# ppc_serial.net
KiCad netlist of a schematic drawn in Altium Designer
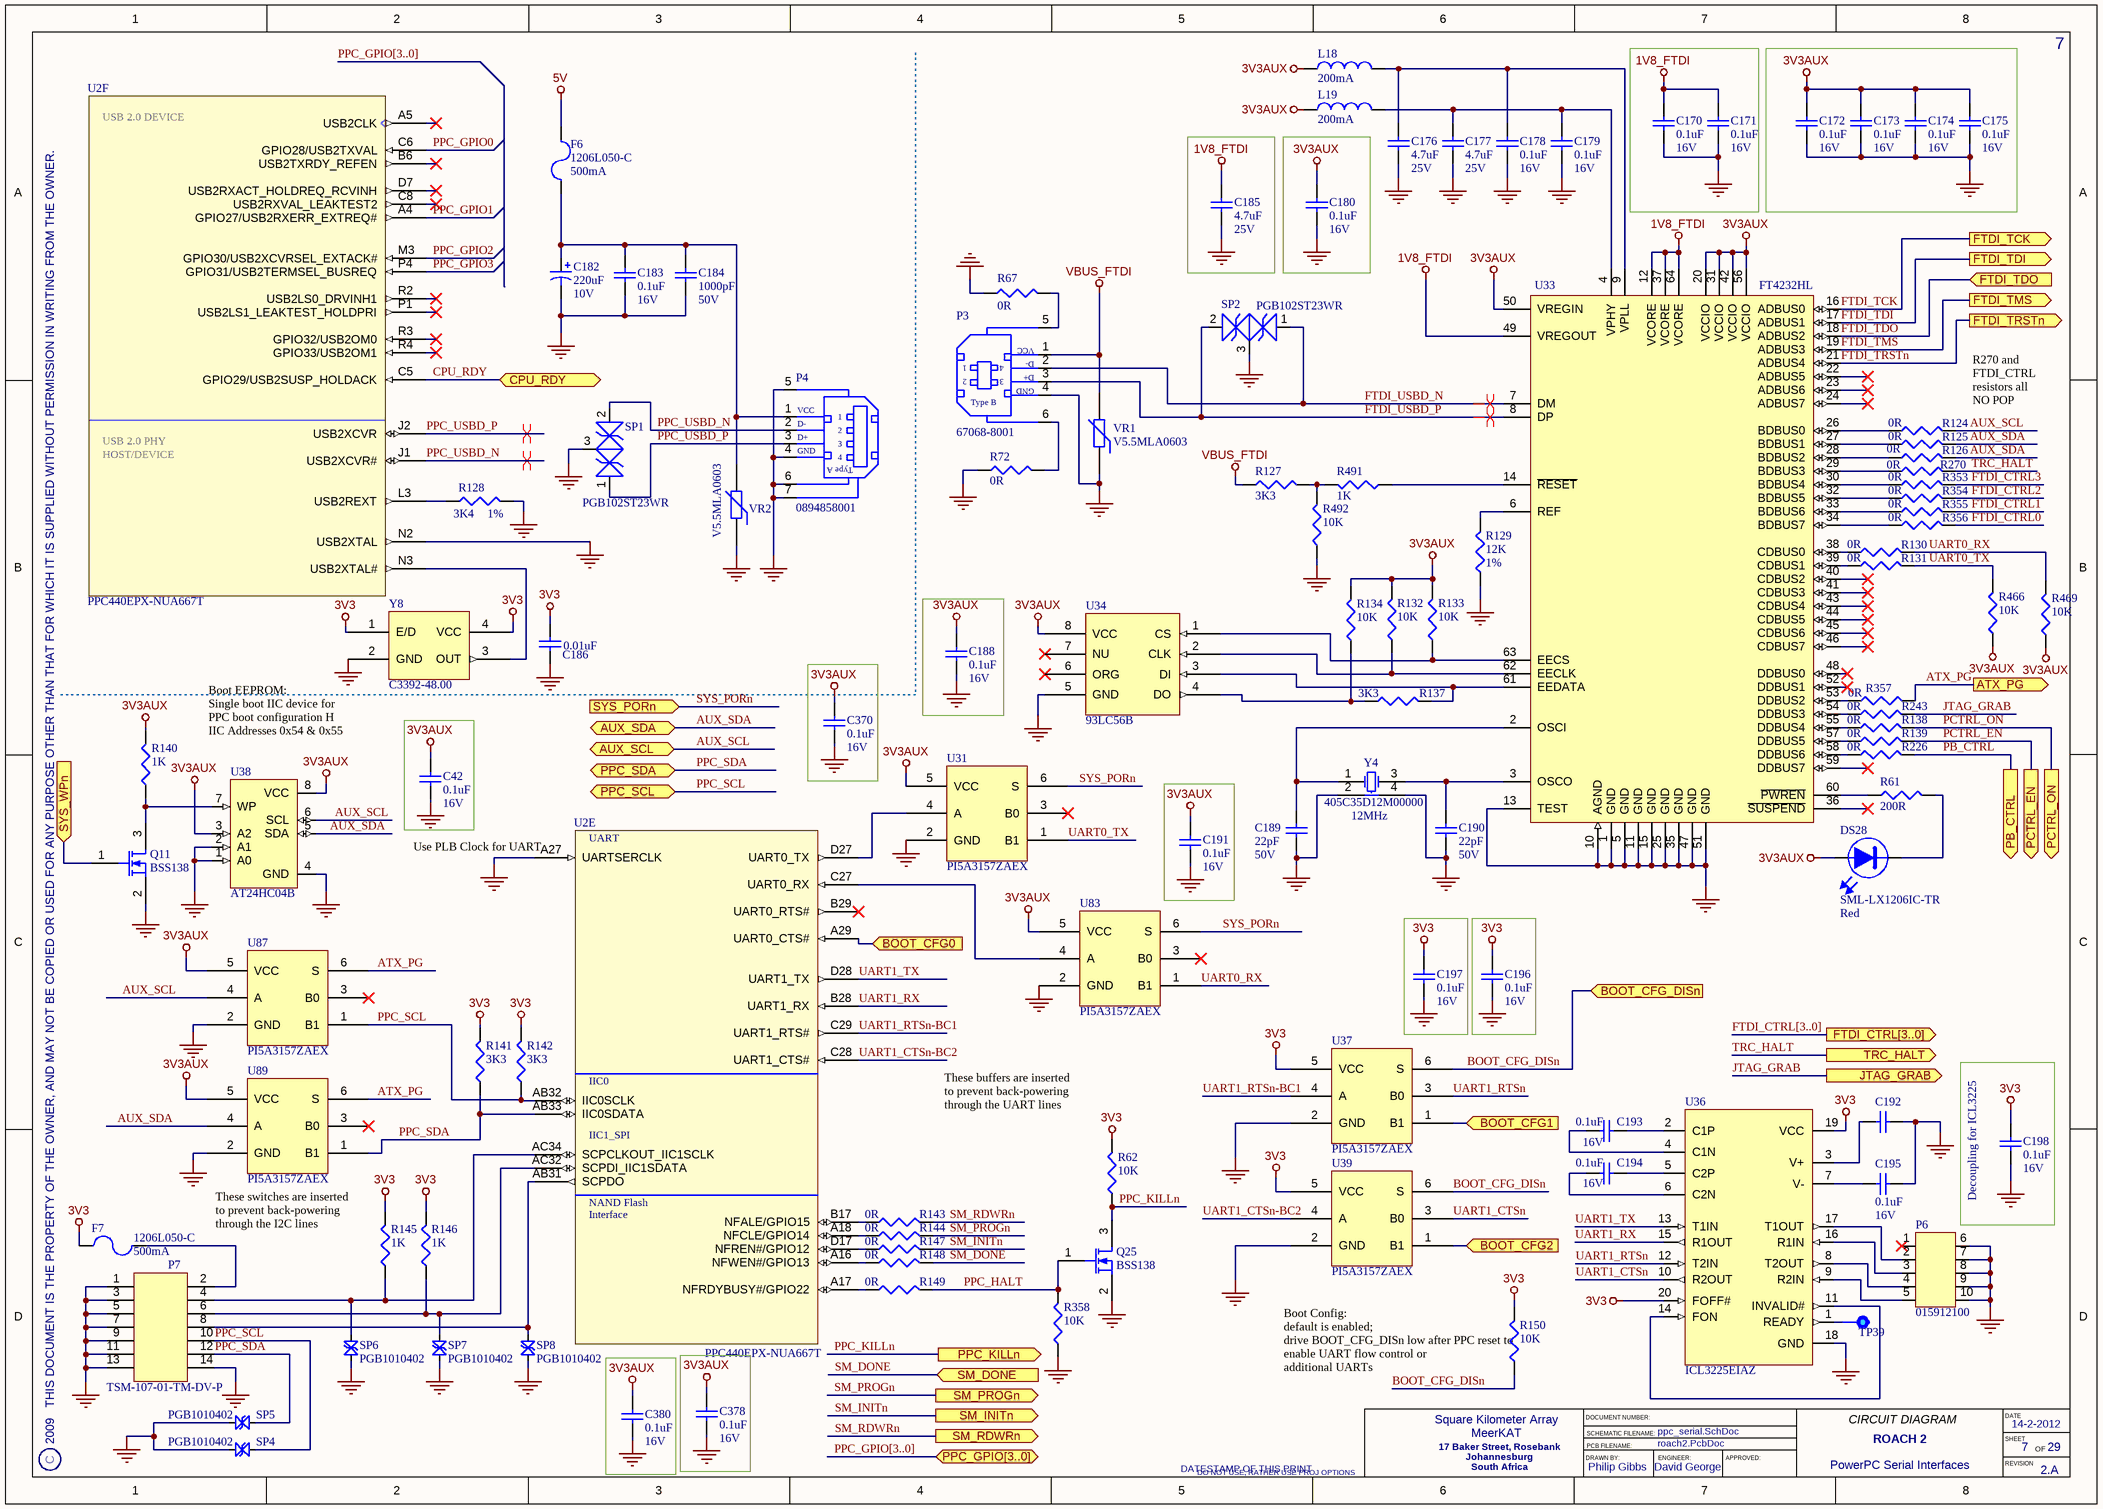
[diagram p0: ppc_serial.SchDoc]

(export (version "E")
  (design (tool "Eeschema 10.0.6"))
  (components
    (comp (ref "C42")
      (value "0.1uF")
      (footprint "CAPC1005X60L")
      (description "0.1uF, Ceramic Capacitor")
      (fields
        (field (name "RATING") "16V")
        (field (name "MANUFACTURER") "VENKEL")
        (field (name "PARTNUM") "C0402X7R160-104KN")
      )
      (libsource (lib "altium_db") (part "CapStd"))
    )
    (comp (ref "C170")
      (value "0.1uF")
      (footprint "CAPC1005X60L")
      (description "0.1uF, Ceramic Capacitor")
      (fields
        (field (name "RATING") "16V")
        (field (name "MANUFACTURER") "VENKEL")
        (field (name "PARTNUM") "C0402X7R160-104KN")
      )
      (libsource (lib "altium_db") (part "CapStd"))
    )
    (comp (ref "C171")
      (value "0.1uF")
      (footprint "CAPC1005X60L")
      (description "0.1uF, Ceramic Capacitor")
      (fields
        (field (name "RATING") "16V")
        (field (name "MANUFACTURER") "VENKEL")
        (field (name "PARTNUM") "C0402X7R160-104KN")
      )
      (libsource (lib "altium_db") (part "CapStd"))
    )
    (comp (ref "C172")
      (value "0.1uF")
      (footprint "CAPC1005X60L")
      (description "0.1uF, Ceramic Capacitor")
      (fields
        (field (name "RATING") "16V")
        (field (name "MANUFACTURER") "VENKEL")
        (field (name "PARTNUM") "C0402X7R160-104KN")
      )
      (libsource (lib "altium_db") (part "CapStd"))
    )
    (comp (ref "C173")
      (value "0.1uF")
      (footprint "CAPC1005X60L")
      (description "0.1uF, Ceramic Capacitor")
      (fields
        (field (name "RATING") "16V")
        (field (name "MANUFACTURER") "VENKEL")
        (field (name "PARTNUM") "C0402X7R160-104KN")
      )
      (libsource (lib "altium_db") (part "CapStd"))
    )
    (comp (ref "C174")
      (value "0.1uF")
      (footprint "CAPC1005X60L")
      (description "0.1uF, Ceramic Capacitor")
      (fields
        (field (name "RATING") "16V")
        (field (name "MANUFACTURER") "VENKEL")
        (field (name "PARTNUM") "C0402X7R160-104KN")
      )
      (libsource (lib "altium_db") (part "CapStd"))
    )
    (comp (ref "C175")
      (value "0.1uF")
      (footprint "CAPC1005X60L")
      (description "0.1uF, Ceramic Capacitor")
      (fields
        (field (name "RATING") "16V")
        (field (name "MANUFACTURER") "VENKEL")
        (field (name "PARTNUM") "C0402X7R160-104KN")
      )
      (libsource (lib "altium_db") (part "CapStd"))
    )
    (comp (ref "C176")
      (value "4.7uF")
      (footprint "CAPC2012X127L")
      (description "4.7uF, Ceramic Capacitor")
      (fields
        (field (name "RATING") "25V")
        (field (name "MANUFACTURER") "MURATA")
        (field (name "PARTNUM") "GRM21BR61E475KA12K")
      )
      (libsource (lib "altium_db") (part "CapStd"))
    )
    (comp (ref "C177")
      (value "4.7uF")
      (footprint "CAPC2012X127L")
      (description "4.7uF, Ceramic Capacitor")
      (fields
        (field (name "RATING") "25V")
        (field (name "MANUFACTURER") "MURATA")
        (field (name "PARTNUM") "GRM21BR61E475KA12K")
      )
      (libsource (lib "altium_db") (part "CapStd"))
    )
    (comp (ref "C178")
      (value "0.1uF")
      (footprint "CAPC1005X60L")
      (description "0.1uF, Ceramic Capacitor")
      (fields
        (field (name "RATING") "16V")
        (field (name "MANUFACTURER") "VENKEL")
        (field (name "PARTNUM") "C0402X7R160-104KN")
      )
      (libsource (lib "altium_db") (part "CapStd"))
    )
    (comp (ref "C179")
      (value "0.1uF")
      (footprint "CAPC1005X60L")
      (description "0.1uF, Ceramic Capacitor")
      (fields
        (field (name "RATING") "16V")
        (field (name "MANUFACTURER") "VENKEL")
        (field (name "PARTNUM") "C0402X7R160-104KN")
      )
      (libsource (lib "altium_db") (part "CapStd"))
    )
    (comp (ref "C180")
      (value "0.1uF")
      (footprint "CAPC1005X60L")
      (description "0.1uF, Ceramic Capacitor")
      (fields
        (field (name "RATING") "16V")
        (field (name "MANUFACTURER") "VENKEL")
        (field (name "PARTNUM") "C0402X7R160-104KN")
      )
      (libsource (lib "altium_db") (part "CapStd"))
    )
    (comp (ref "C182")
      (value "220uF")
      (footprint "CAPMP7343X430L")
      (description "220uF, Solid Tantalum Chip Capacitor")
      (fields
        (field (name "RATING") "10V")
        (field (name "MANUFACTURER") "KEMET")
        (field (name "PARTNUM") "T491X227M010AT")
      )
      (libsource (lib "altium_db") (part "CapPol"))
    )
    (comp (ref "C183")
      (value "0.1uF")
      (footprint "CAPC1005X60L")
      (description "0.1uF, Ceramic Capacitor")
      (fields
        (field (name "RATING") "16V")
        (field (name "MANUFACTURER") "VENKEL")
        (field (name "PARTNUM") "C0402X7R160-104KN")
      )
      (libsource (lib "altium_db") (part "CapStd"))
    )
    (comp (ref "C184")
      (value "1000pF")
      (footprint "CAPC1005X55L")
      (description "1000pF, Ceramic Capacitor")
      (fields
        (field (name "RATING") "50V")
        (field (name "MANUFACTURER") "MURATA")
        (field (name "PARTNUM") "GRM155R61H102KA01D")
      )
      (libsource (lib "altium_db") (part "CapStd"))
    )
    (comp (ref "C185")
      (value "4.7uF")
      (footprint "CAPC2012X127L")
      (description "4.7uF, Ceramic Capacitor")
      (fields
        (field (name "RATING") "25V")
        (field (name "MANUFACTURER") "MURATA")
        (field (name "PARTNUM") "GRM21BR61E475KA12K")
      )
      (libsource (lib "altium_db") (part "CapStd"))
    )
    (comp (ref "C186")
      (value "0.01uF")
      (footprint "CAPC1005X55L")
      (description "0.01uF, Ceramic Capacitor")
      (fields (field (name "MANUFACTURER") "MURATA") (field (name "PARTNUM") "GRM155R71E103KA01D"))
      (libsource (lib "Altium_DB") (part "CapStd"))
    )
    (comp (ref "C188")
      (value "0.1uF")
      (footprint "CAPC1005X60L")
      (description "0.1uF, Ceramic Capacitor")
      (fields
        (field (name "RATING") "16V")
        (field (name "MANUFACTURER") "VENKEL")
        (field (name "PARTNUM") "C0402X7R160-104KN")
      )
      (libsource (lib "altium_db") (part "CapStd"))
    )
    (comp (ref "C189")
      (value "22pF")
      (footprint "CAPC1005X55L")
      (description "22pF, Ceramic Capacitor")
      (fields
        (field (name "RATING") "50V")
        (field (name "MANUFACTURER") "MURATA")
        (field (name "PARTNUM") "GRM1555C1H220JA01D")
      )
      (libsource (lib "altium_db") (part "CapStd"))
    )
    (comp (ref "C190")
      (value "22pF")
      (footprint "CAPC1005X55L")
      (description "22pF, Ceramic Capacitor")
      (fields
        (field (name "RATING") "50V")
        (field (name "MANUFACTURER") "MURATA")
        (field (name "PARTNUM") "GRM1555C1H220JA01D")
      )
      (libsource (lib "altium_db") (part "CapStd"))
    )
    (comp (ref "C191")
      (value "0.1uF")
      (footprint "CAPC1005X60L")
      (description "0.1uF, Ceramic Capacitor")
      (fields
        (field (name "RATING") "16V")
        (field (name "MANUFACTURER") "VENKEL")
        (field (name "PARTNUM") "C0402X7R160-104KN")
      )
      (libsource (lib "altium_db") (part "CapStd"))
    )
    (comp (ref "C192")
      (value "~")
      (footprint "CAPC1005X60L")
      (description "0.1uF, Ceramic Capacitor")
      (fields (field (name "MANUFACTURER") "VENKEL") (field (name "PARTNUM") "C0402X7R160-104KN"))
      (libsource (lib "altium_db") (part "CapStd"))
    )
    (comp (ref "C193")
      (value "0.1uF")
      (footprint "CAPC1005X60L")
      (description "0.1uF, Ceramic Capacitor")
      (fields
        (field (name "RATING") "16V")
        (field (name "MANUFACTURER") "VENKEL")
        (field (name "PARTNUM") "C0402X7R160-104KN")
      )
      (libsource (lib "altium_db") (part "CapStd"))
    )
    (comp (ref "C194")
      (value "0.1uF")
      (footprint "CAPC1005X60L")
      (description "0.1uF, Ceramic Capacitor")
      (fields
        (field (name "RATING") "16V")
        (field (name "MANUFACTURER") "VENKEL")
        (field (name "PARTNUM") "C0402X7R160-104KN")
      )
      (libsource (lib "altium_db") (part "CapStd"))
    )
    (comp (ref "C195")
      (value "0.1uF")
      (footprint "CAPC1005X60L")
      (description "0.1uF, Ceramic Capacitor")
      (fields
        (field (name "RATING") "16V")
        (field (name "MANUFACTURER") "VENKEL")
        (field (name "PARTNUM") "C0402X7R160-104KN")
      )
      (libsource (lib "altium_db") (part "CapStd"))
    )
    (comp (ref "C196")
      (value "0.1uF")
      (footprint "CAPC1005X60L")
      (description "0.1uF, Ceramic Capacitor")
      (fields
        (field (name "RATING") "16V")
        (field (name "MANUFACTURER") "VENKEL")
        (field (name "PARTNUM") "C0402X7R160-104KN")
      )
      (libsource (lib "altium_db") (part "CapStd"))
    )
    (comp (ref "C197")
      (value "0.1uF")
      (footprint "CAPC1005X60L")
      (description "0.1uF, Ceramic Capacitor")
      (fields
        (field (name "RATING") "16V")
        (field (name "MANUFACTURER") "VENKEL")
        (field (name "PARTNUM") "C0402X7R160-104KN")
      )
      (libsource (lib "altium_db") (part "CapStd"))
    )
    (comp (ref "C198")
      (value "0.1uF")
      (footprint "CAPC1005X60L")
      (description "0.1uF, Ceramic Capacitor")
      (fields
        (field (name "RATING") "16V")
        (field (name "MANUFACTURER") "VENKEL")
        (field (name "PARTNUM") "C0402X7R160-104KN")
      )
      (libsource (lib "altium_db") (part "CapStd"))
    )
    (comp (ref "C370")
      (value "0.1uF")
      (footprint "CAPC1005X60L")
      (description "0.1uF, Ceramic Capacitor")
      (fields
        (field (name "RATING") "16V")
        (field (name "MANUFACTURER") "VENKEL")
        (field (name "PARTNUM") "C0402X7R160-104KN")
      )
      (libsource (lib "altium_db") (part "CapStd"))
    )
    (comp (ref "C378")
      (value "0.1uF")
      (footprint "CAPC1005X60L")
      (description "0.1uF, Ceramic Capacitor")
      (fields
        (field (name "RATING") "16V")
        (field (name "MANUFACTURER") "VENKEL")
        (field (name "PARTNUM") "C0402X7R160-104KN")
      )
      (libsource (lib "altium_db") (part "CapStd"))
    )
    (comp (ref "C380")
      (value "0.1uF")
      (footprint "CAPC1005X60L")
      (description "0.1uF, Ceramic Capacitor")
      (fields
        (field (name "RATING") "16V")
        (field (name "MANUFACTURER") "VENKEL")
        (field (name "PARTNUM") "C0402X7R160-104KN")
      )
      (libsource (lib "altium_db") (part "CapStd"))
    )
    (comp (ref "DS28")
      (value "SML-LX1206IC-TR")
      (footprint "LEDC3216X120N")
      (description "Red, Surface mount, LED, 1206")
      (fields (field (name "COLOUR") "Red") (field (name "MANUFACTURER") "LUMEX"))
      (libsource (lib "altium_db") (part "LEDSTD"))
    )
    (comp (ref "F6")
      (value "1206L050-C")
      (footprint "FUSMC3215X145")
      (description "Resettable, Surface mount Fuse")
      (fields
        (field (name "MANUFACTURER") "Littelfuse")
        (field (name "PARTNUM") "1206L050-C")
        (field (name "RATING") "500mA")
      )
      (libsource (lib "altium_db") (part "FuseStd"))
    )
    (comp (ref "F7")
      (value "1206L050-C")
      (footprint "FUSMC3215X145")
      (description "Resettable, Surface mount Fuse")
      (fields
        (field (name "MANUFACTURER") "Littelfuse")
        (field (name "PARTNUM") "1206L050-C")
        (field (name "RATING") "500mA")
      )
      (libsource (lib "altium_db") (part "FuseStd"))
    )
    (comp (ref "L18")
      (value "600R")
      (footprint "INDC2012X130L")
      (description "600 Ohm, Chip Ferrite Bead")
      (fields
        (field (name "MANUFACTURER") "Murata")
        (field (name "PARTNUM") "BLM21BD601SN1")
        (field (name "RATING") "200mA")
      )
      (libsource (lib "altium_db") (part "IndStd"))
    )
    (comp (ref "L19")
      (value "600R")
      (footprint "INDC2012X130L")
      (description "600 Ohm, Chip Ferrite Bead")
      (fields
        (field (name "MANUFACTURER") "Murata")
        (field (name "PARTNUM") "BLM21BD601SN1")
        (field (name "RATING") "200mA")
      )
      (libsource (lib "altium_db") (part "IndStd"))
    )
    (comp (ref "P3")
      (value "67068-8001")
      (footprint "MOLEX_67068-8001")
      (description "Right angle, Through-hole, USB Type B Receptacle")
      (fields (field (name "PARTNUM") "67068-8001") (field (name "MANUFACTURER") "Molex"))
      (libsource (lib "altium_db") (part "USB_TYPE_B_GENERIC"))
    )
    (comp (ref "P4")
      (value "USB_TYPEA_TYCO")
      (footprint "MOLEX_0894858001")
      (description "Right angle, Through-hole, USB Type A Receptacle")
      (fields (field (name "PARTNUM") "0894858001"))
      (libsource (lib "altium_db") (part "0894858001"))
    )
    (comp (ref "P6")
      (value "015912100")
      (footprint "MOLEX_0015912100")
      (description "2x5, 2.54 mm Pitch, Male Header")
      (fields (field (name "MANUFACTURER") "Molex") (field (name "PARTNUM") "015912100"))
      (libsource (lib "altium_db") (part "con_hdr_2x5"))
    )
    (comp (ref "P7")
      (value "TSM-107-01-TM-DV-P")
      (footprint "SAMTEC_TSM-107-01-TM-DV-P")
      (description "2x7, 2.54 mm Pitch, Male Header")
      (fields (field (name "PARTNUM") "TSM-107-01-TM-DV-P") (field (name "MANUFACTURER") "SAMTEC"))
      (libsource (lib "altium_db") (part "con_hdr_2x7"))
    )
    (comp (ref "Q11")
      (value "BSS138")
      (footprint "SOT95P245X110-3N")
      (description "N-Channel Logic Level Enhancement Mode Field Effect Transistor")
      (fields (field (name "MANUFACTURER") "Fairchild Semiconductor"))
      (libsource (lib "altium_db") (part "BSS138"))
    )
    (comp (ref "Q25")
      (value "BSS138")
      (footprint "SOT95P245X110-3N")
      (description "N-Channel Logic Level Enhancement Mode Field Effect Transistor")
      (fields (field (name "MANUFACTURER") "Fairchild Semiconductor"))
      (libsource (lib "altium_db") (part "BSS138"))
    )
    (comp (ref "R61")
      (value "200R")
      (footprint "RESC1005X40L")
      (description "200R, 1.1mm x 0.5mm, Thick Film Resistor")
      (fields (field (name "MANUFACTURER") "ROYALOHM") (field (name "PARTNUM") "0402WGF0201T1E"))
      (libsource (lib "altium_db") (part "ResStd"))
    )
    (comp (ref "R62")
      (value "10K")
      (footprint "RESC1005X40L")
      (description "10K, 1.1mm x 0.5mm, Thick Film Resistor")
      (fields (field (name "MANUFACTURER") "ROYALOHM") (field (name "PARTNUM") "0402WGJ0103T1E"))
      (libsource (lib "altium_db") (part "ResStd"))
    )
    (comp (ref "R67")
      (value "0R")
      (footprint "RESC1005X40L")
      (description "0R, 1.1mm x 0.5mm, Thick Film Resistor")
      (fields (field (name "MANUFACTURER") "ROYALOHM") (field (name "PARTNUM") "0402WG00000T1E"))
      (libsource (lib "altium_db") (part "ResStd"))
    )
    (comp (ref "R72")
      (value "0R")
      (footprint "RESC1005X40L")
      (description "0R, 1.1mm x 0.5mm, Thick Film Resistor")
      (fields (field (name "MANUFACTURER") "ROYALOHM") (field (name "PARTNUM") "0402WG00000T1E"))
      (libsource (lib "altium_db") (part "ResStd"))
    )
    (comp (ref "R124")
      (value "0R")
      (footprint "RESC1005X40L")
      (description "0R, 1.1mm x 0.5mm, Thick Film Resistor")
      (fields (field (name "MANUFACTURER") "ROYALOHM") (field (name "PARTNUM") "0402WG00000T1E"))
      (libsource (lib "altium_db") (part "ResStd"))
    )
    (comp (ref "R125")
      (value "0R")
      (footprint "RESC1005X40L")
      (description "0R, 1.1mm x 0.5mm, Thick Film Resistor")
      (fields (field (name "MANUFACTURER") "ROYALOHM") (field (name "PARTNUM") "0402WG00000T1E"))
      (libsource (lib "altium_db") (part "ResStd"))
    )
    (comp (ref "R126")
      (value "0R")
      (footprint "RESC1005X40L")
      (description "0R, 1.1mm x 0.5mm, Thick Film Resistor")
      (fields (field (name "MANUFACTURER") "ROYALOHM") (field (name "PARTNUM") "0402WG00000T1E"))
      (libsource (lib "altium_db") (part "ResStd"))
    )
    (comp (ref "R127")
      (value "3K3")
      (footprint "RESC1005X40L")
      (description "3K3, 1.1mm x 0.5mm, Thick Film Resistor")
      (fields (field (name "MANUFACTURER") "ROYALOHM") (field (name "PARTNUM") "0402WGJ0332T1E"))
      (libsource (lib "altium_db") (part "ResStd"))
    )
    (comp (ref "R128")
      (value "3K4")
      (footprint "RESC1005X40L")
      (description "3K4, 1.1mm x 0.5mm, Thick Film Resistor")
      (fields
        (field (name "MANUFACTURER") "ROYALOHM")
        (field (name "PARTNUM") "0402WGF0342T1E")
        (field (name "TOLERANCE") "1%")
      )
      (libsource (lib "altium_db") (part "ResStd"))
    )
    (comp (ref "R129")
      (value "12K")
      (footprint "RESC1005X40L")
      (description "12K, 1.1mm x 0.5mm, Thick Film Resistor")
      (fields
        (field (name "MANUFACTURER") "ROYALOHM")
        (field (name "PARTNUM") "0402WGF0123T1E")
        (field (name "TOLERANCE") "1%")
      )
      (libsource (lib "altium_db") (part "ResStd"))
    )
    (comp (ref "R130")
      (value "0R")
      (footprint "RESC1005X40L")
      (description "0R, 1.1mm x 0.5mm, Thick Film Resistor")
      (fields (field (name "MANUFACTURER") "ROYALOHM") (field (name "PARTNUM") "0402WG00000T1E"))
      (libsource (lib "altium_db") (part "ResStd"))
    )
    (comp (ref "R131")
      (value "0R")
      (footprint "RESC1005X40L")
      (description "0R, 1.1mm x 0.5mm, Thick Film Resistor")
      (fields (field (name "MANUFACTURER") "ROYALOHM") (field (name "PARTNUM") "0402WG00000T1E"))
      (libsource (lib "altium_db") (part "ResStd"))
    )
    (comp (ref "R132")
      (value "10K")
      (footprint "RESC1005X40L")
      (description "10K, 1.1mm x 0.5mm, Thick Film Resistor")
      (fields (field (name "MANUFACTURER") "ROYALOHM") (field (name "PARTNUM") "0402WGJ0103T1E"))
      (libsource (lib "altium_db") (part "ResStd"))
    )
    (comp (ref "R133")
      (value "10K")
      (footprint "RESC1005X40L")
      (description "10K, 1.1mm x 0.5mm, Thick Film Resistor")
      (fields (field (name "MANUFACTURER") "ROYALOHM") (field (name "PARTNUM") "0402WGJ0103T1E"))
      (libsource (lib "altium_db") (part "ResStd"))
    )
    (comp (ref "R134")
      (value "10K")
      (footprint "RESC1005X40L")
      (description "10K, 1.1mm x 0.5mm, Thick Film Resistor")
      (fields (field (name "MANUFACTURER") "ROYALOHM") (field (name "PARTNUM") "0402WGJ0103T1E"))
      (libsource (lib "altium_db") (part "ResStd"))
    )
    (comp (ref "R137")
      (value "3K3")
      (footprint "RESC1005X40L")
      (description "3K3, 1.1mm x 0.5mm, Thick Film Resistor")
      (fields (field (name "MANUFACTURER") "ROYALOHM") (field (name "PARTNUM") "0402WGJ0332T1E"))
      (libsource (lib "altium_db") (part "ResStd"))
    )
    (comp (ref "R138")
      (value "0R")
      (footprint "RESC1005X40L")
      (description "0R, 1.1mm x 0.5mm, Thick Film Resistor")
      (fields (field (name "MANUFACTURER") "ROYALOHM") (field (name "PARTNUM") "0402WG00000T1E"))
      (libsource (lib "altium_db") (part "ResStd"))
    )
    (comp (ref "R139")
      (value "0R")
      (footprint "RESC1005X40L")
      (description "0R, 1.1mm x 0.5mm, Thick Film Resistor")
      (fields (field (name "MANUFACTURER") "ROYALOHM") (field (name "PARTNUM") "0402WG00000T1E"))
      (libsource (lib "altium_db") (part "ResStd"))
    )
    (comp (ref "R140")
      (value "1K")
      (footprint "RESC1005X40L")
      (description "1K, 1.1mm x 0.5mm, Thick Film Resistor")
      (fields (field (name "MANUFACTURER") "ROYALOHM") (field (name "PARTNUM") "0402WGJ0102T1E"))
      (libsource (lib "altium_db") (part "ResStd"))
    )
    (comp (ref "R141")
      (value "3K3")
      (footprint "RESC1005X40L")
      (description "3K3, 1.1mm x 0.5mm, Thick Film Resistor")
      (fields (field (name "MANUFACTURER") "ROYALOHM") (field (name "PARTNUM") "0402WGJ0332T1E"))
      (libsource (lib "Altium_DB") (part "ResStd"))
    )
    (comp (ref "R142")
      (value "3K3")
      (footprint "RESC1005X40L")
      (description "3K3, 1.1mm x 0.5mm, Thick Film Resistor")
      (fields (field (name "MANUFACTURER") "ROYALOHM") (field (name "PARTNUM") "0402WGJ0332T1E"))
      (libsource (lib "Altium_DB") (part "ResStd"))
    )
    (comp (ref "R143")
      (value "0R")
      (footprint "RESC1005X40L")
      (description "0R, 1.1mm x 0.5mm, Thick Film Resistor")
      (fields (field (name "MANUFACTURER") "ROYALOHM") (field (name "PARTNUM") "0402WG00000T1E"))
      (libsource (lib "altium_db") (part "ResStd"))
    )
    (comp (ref "R144")
      (value "0R")
      (footprint "RESC1005X40L")
      (description "0R, 1.1mm x 0.5mm, Thick Film Resistor")
      (fields (field (name "MANUFACTURER") "ROYALOHM") (field (name "PARTNUM") "0402WG00000T1E"))
      (libsource (lib "altium_db") (part "ResStd"))
    )
    (comp (ref "R145")
      (value "1K")
      (footprint "RESC1005X40L")
      (description "1K, 1.1mm x 0.5mm, Thick Film Resistor")
      (fields (field (name "MANUFACTURER") "ROYALOHM") (field (name "PARTNUM") "0402WGJ0102T1E"))
      (libsource (lib "altium_db") (part "ResStd"))
    )
    (comp (ref "R146")
      (value "1K")
      (footprint "RESC1005X40L")
      (description "1K, 1.1mm x 0.5mm, Thick Film Resistor")
      (fields (field (name "MANUFACTURER") "ROYALOHM") (field (name "PARTNUM") "0402WGJ0102T1E"))
      (libsource (lib "altium_db") (part "ResStd"))
    )
    (comp (ref "R147")
      (value "0R")
      (footprint "RESC1005X40L")
      (description "0R, 1.1mm x 0.5mm, Thick Film Resistor")
      (fields (field (name "MANUFACTURER") "ROYALOHM") (field (name "PARTNUM") "0402WG00000T1E"))
      (libsource (lib "altium_db") (part "ResStd"))
    )
    (comp (ref "R148")
      (value "0R")
      (footprint "RESC1005X40L")
      (description "0R, 1.1mm x 0.5mm, Thick Film Resistor")
      (fields (field (name "MANUFACTURER") "ROYALOHM") (field (name "PARTNUM") "0402WG00000T1E"))
      (libsource (lib "altium_db") (part "ResStd"))
    )
    (comp (ref "R149")
      (value "0R")
      (footprint "RESC1005X40L")
      (description "0R, 1.1mm x 0.5mm, Thick Film Resistor")
      (fields (field (name "MANUFACTURER") "ROYALOHM") (field (name "PARTNUM") "0402WG00000T1E"))
      (libsource (lib "altium_db") (part "ResStd"))
    )
    (comp (ref "R150")
      (value "10K")
      (footprint "RESC1005X40L")
      (description "10K, 1.1mm x 0.5mm, Thick Film Resistor")
      (fields (field (name "MANUFACTURER") "ROYALOHM") (field (name "PARTNUM") "0402WGJ0103T1E"))
      (libsource (lib "altium_db") (part "ResStd"))
    )
    (comp (ref "R226")
      (value "0R")
      (footprint "RESC1005X40L")
      (description "0R, 1.1mm x 0.5mm, Thick Film Resistor")
      (fields (field (name "MANUFACTURER") "ROYALOHM") (field (name "PARTNUM") "0402WG00000T1E"))
      (libsource (lib "altium_db") (part "ResStd"))
    )
    (comp (ref "R243")
      (value "0R")
      (footprint "RESC1005X40L")
      (description "0R, 1.1mm x 0.5mm, Thick Film Resistor")
      (fields (field (name "MANUFACTURER") "ROYALOHM") (field (name "PARTNUM") "0402WG00000T1E"))
      (libsource (lib "altium_db") (part "ResStd"))
    )
    (comp (ref "R270")
      (value "0R")
      (footprint "RESC1005X40L")
      (description "0R, 1.1mm x 0.5mm, Thick Film Resistor")
      (fields (field (name "MANUFACTURER") "ROYALOHM") (field (name "PARTNUM") "0402WG00000T1E"))
      (libsource (lib "altium_db") (part "ResStd"))
    )
    (comp (ref "R353")
      (value "0R")
      (footprint "RESC1005X40L")
      (description "0R, 1.1mm x 0.5mm, Thick Film Resistor")
      (fields (field (name "MANUFACTURER") "ROYALOHM") (field (name "PARTNUM") "0402WG00000T1E"))
      (libsource (lib "altium_db") (part "ResStd"))
    )
    (comp (ref "R354")
      (value "0R")
      (footprint "RESC1005X40L")
      (description "0R, 1.1mm x 0.5mm, Thick Film Resistor")
      (fields (field (name "MANUFACTURER") "ROYALOHM") (field (name "PARTNUM") "0402WG00000T1E"))
      (libsource (lib "altium_db") (part "ResStd"))
    )
    (comp (ref "R355")
      (value "0R")
      (footprint "RESC1005X40L")
      (description "0R, 1.1mm x 0.5mm, Thick Film Resistor")
      (fields (field (name "MANUFACTURER") "ROYALOHM") (field (name "PARTNUM") "0402WG00000T1E"))
      (libsource (lib "altium_db") (part "ResStd"))
    )
    (comp (ref "R356")
      (value "0R")
      (footprint "RESC1005X40L")
      (description "0R, 1.1mm x 0.5mm, Thick Film Resistor")
      (fields (field (name "MANUFACTURER") "ROYALOHM") (field (name "PARTNUM") "0402WG00000T1E"))
      (libsource (lib "altium_db") (part "ResStd"))
    )
    (comp (ref "R357")
      (value "0R")
      (footprint "RESC1005X40L")
      (description "0R, 1.1mm x 0.5mm, Thick Film Resistor")
      (fields (field (name "MANUFACTURER") "ROYALOHM") (field (name "PARTNUM") "0402WG00000T1E"))
      (libsource (lib "altium_db") (part "ResStd"))
    )
    (comp (ref "R358")
      (value "10K")
      (footprint "RESC1005X40L")
      (description "10K, 1.1mm x 0.5mm, Thick Film Resistor")
      (fields (field (name "MANUFACTURER") "ROYALOHM") (field (name "PARTNUM") "0402WGJ0103T1E"))
      (libsource (lib "altium_db") (part "ResStd"))
    )
    (comp (ref "R466")
      (value "10K")
      (footprint "RESC1005X40L")
      (description "10K, 1.1mm x 0.5mm, Thick Film Resistor")
      (fields (field (name "MANUFACTURER") "ROYALOHM") (field (name "PARTNUM") "0402WGJ0103T1E"))
      (libsource (lib "altium_db") (part "ResStd"))
    )
    (comp (ref "R469")
      (value "10K")
      (footprint "RESC1005X40L")
      (description "10K, 1.1mm x 0.5mm, Thick Film Resistor")
      (fields (field (name "MANUFACTURER") "ROYALOHM") (field (name "PARTNUM") "0402WGJ0103T1E"))
      (libsource (lib "altium_db") (part "ResStd"))
    )
    (comp (ref "R491")
      (value "1K")
      (footprint "RESC1005X40L")
      (description "1K, 1.1mm x 0.5mm, Thick Film Resistor")
      (fields (field (name "MANUFACTURER") "ROYALOHM") (field (name "PARTNUM") "0402WGJ0102T1E"))
      (libsource (lib "altium_db") (part "ResStd"))
    )
    (comp (ref "R492")
      (value "10K")
      (footprint "RESC1005X40L")
      (description "10K, 1.1mm x 0.5mm, Thick Film Resistor")
      (fields (field (name "MANUFACTURER") "ROYALOHM") (field (name "PARTNUM") "0402WGJ0103T1E"))
      (libsource (lib "altium_db") (part "ResStd"))
    )
    (comp (ref "SP1")
      (value "PGB102ST23WR")
      (footprint "SOT95P245X110-3N")
      (description "Ultra-low Capacitance, Surface mount ESD Suppressor")
      (fields (field (name "PARTNUM") "PGB102ST23WR") (field (name "MANUFACTURER") "Littelfuse"))
      (libsource (lib "altium_db") (part "PGB002ST23WR"))
    )
    (comp (ref "SP2")
      (value "PGB102ST23WR")
      (footprint "SOT95P245X110-3N")
      (description "Ultra-low Capacitance, Surface mount ESD Suppressor")
      (fields (field (name "PARTNUM") "PGB102ST23WR") (field (name "MANUFACTURER") "Littelfuse"))
      (libsource (lib "altium_db") (part "PGB002ST23WR"))
    )
    (comp (ref "SP4")
      (value "PGB1010402")
      (footprint "PGB1010402")
      (description "Surface Mount Polymeric ESD Suppressor in an 0402 package")
      (fields (field (name "PARTNUM") "PGB1010402"))
      (libsource (lib "altium_db") (part "PGB1010402"))
    )
    (comp (ref "SP5")
      (value "PGB1010402")
      (footprint "PGB1010402")
      (description "Surface Mount Polymeric ESD Suppressor in an 0402 package")
      (fields (field (name "PARTNUM") "PGB1010402"))
      (libsource (lib "altium_db") (part "PGB1010402"))
    )
    (comp (ref "SP6")
      (value "PGB1010402")
      (footprint "PGB1010402")
      (description "Surface Mount Polymeric ESD Suppressor in an 0402 package")
      (fields (field (name "PARTNUM") "PGB1010402"))
      (libsource (lib "altium_db") (part "PGB1010402"))
    )
    (comp (ref "SP7")
      (value "PGB1010402")
      (footprint "PGB1010402")
      (description "Surface Mount Polymeric ESD Suppressor in an 0402 package")
      (fields (field (name "PARTNUM") "PGB1010402"))
      (libsource (lib "altium_db") (part "PGB1010402"))
    )
    (comp (ref "SP8")
      (value "PGB1010402")
      (footprint "PGB1010402")
      (description "Surface Mount Polymeric ESD Suppressor in an 0402 package")
      (fields (field (name "PARTNUM") "PGB1010402"))
      (libsource (lib "altium_db") (part "PGB1010402"))
    )
    (comp (ref "TP39")
      (value "Testpoint")
      (footprint "TP100")
      (description "1mm Diameter, through-hole, Circular Test-point")
      (libsource (lib "altium_db") (part "Testpoint"))
    )
    (comp (ref "U2")
      (value "PPC440EPX-NUA667T")
      (footprint "TE-PBGA680")
      (description "667MHz, non-RoHS, PPC440EPx uProcessor")
      (fields (field (name "MANUFACTURER") "Applied Micro"))
      (libsource (lib "altium_db") (part "PPC440EPX"))
    )
    (comp (ref "U31")
      (value "PI5A3157ZAEX")
      (footprint "SC70-6")
      (description "Low voltage SPDT Analogue Switch")
      (fields (field (name "MANUFACTURER") "PERICOM"))
      (libsource (lib "altium_db") (part "PI5A3157ZAEX"))
    )
    (comp (ref "U33")
      (value "FT4232HL")
      (footprint "QFN64")
      (description "Quad High Speed USB to Multipurpose UART/MPSSE")
      (fields (field (name "MANUFACTURER") "FTDI"))
      (libsource (lib "altium_db") (part "FT4232HL"))
    )
    (comp (ref "U34")
      (value "93LC56B")
      (footprint "SOIC150-8_N")
      (description "2K Microwire Compatible Serial EEPROM")
      (fields (field (name "MANUFACTURER") "Microchip") (field (name "PARTNUM") "93LC56B/SN"))
      (libsource (lib "altium_db") (part "93LC56B"))
    )
    (comp (ref "U36")
      (value "ICL3225EIAZ")
      (footprint "SSOP20_M")
      (description "Low-power RS232 transceivers")
      (fields (field (name "MANUFACTURER") "Intersil"))
      (libsource (lib "altium_db") (part "ICL3225"))
    )
    (comp (ref "U37")
      (value "PI5A3157ZAEX")
      (footprint "SC70-6")
      (description "Low voltage SPDT Analogue Switch")
      (fields (field (name "MANUFACTURER") "PERICOM"))
      (libsource (lib "altium_db") (part "PI5A3157ZAEX"))
    )
    (comp (ref "U38")
      (value "AT24HC04B")
      (footprint "TSSOP-8A2")
      (description "4K Serial EEPROM")
      (fields (field (name "MANUFACTURER") "Atmel"))
      (libsource (lib "altium_db") (part "AT24HC04B"))
    )
    (comp (ref "U39")
      (value "PI5A3157ZAEX")
      (footprint "SC70-6")
      (description "Low voltage SPDT Analogue Switch")
      (fields (field (name "MANUFACTURER") "PERICOM"))
      (libsource (lib "altium_db") (part "PI5A3157ZAEX"))
    )
    (comp (ref "U83")
      (value "PI5A3157ZAEX")
      (footprint "SC70-6")
      (description "Low voltage SPDT Analogue Switch")
      (fields (field (name "MANUFACTURER") "PERICOM"))
      (libsource (lib "altium_db") (part "PI5A3157ZAEX"))
    )
    (comp (ref "U87")
      (value "PI5A3157ZAEX")
      (footprint "SC70-6")
      (description "Low voltage SPDT Analogue Switch")
      (fields (field (name "MANUFACTURER") "PERICOM"))
      (libsource (lib "altium_db") (part "PI5A3157ZAEX"))
    )
    (comp (ref "U89")
      (value "PI5A3157ZAEX")
      (footprint "SC70-6")
      (description "Low voltage SPDT Analogue Switch")
      (fields (field (name "MANUFACTURER") "PERICOM"))
      (libsource (lib "altium_db") (part "PI5A3157ZAEX"))
    )
    (comp (ref "VR1")
      (value "V5.5MLA0603")
      (footprint "VAR_V5_5MLA0603")
      (description "Multilayer Transient Voltage Surge Suppressing Varistor")
      (fields (field (name "MANUFACTURER") "Littelfuse") (field (name "PARTNUM") "V5.5MLA0603"))
      (libsource (lib "altium_db") (part "Varistor"))
    )
    (comp (ref "VR2")
      (value "V5.5MLA0603")
      (footprint "VAR_V5_5MLA0603")
      (description "Multilayer Transient Voltage Surge Suppressing Varistor")
      (fields (field (name "MANUFACTURER") "Littelfuse") (field (name "PARTNUM") "V5.5MLA0603"))
      (libsource (lib "altium_db") (part "Varistor"))
    )
    (comp (ref "Y4")
      (value "405C35D12M00000")
      (footprint "405XXXXXXMXXXXX")
      (description "12 MHz, Surface mount, Crystal Oscillator")
      (fields
        (field (name "PARTNUM") "405C35D12M00000")
        (field (name "FREQUENCY") "12MHz")
        (field (name "MANUFACTURER") "CTS")
      )
      (libsource (lib "altium_db") (part "405XXXXXXMXXXXX"))
    )
    (comp (ref "Y8")
      (value "C3392-48.00")
      (footprint "CB3X-X-XMX")
      (description "48 MHz, 3V3, Surface mount, Clock Oscillator")
      (fields (field (name "MANUFACTURER") "Crystek"))
      (libsource (lib "Altium_DB") (part "C3392-48.00"))
    )
  )
  (nets
    (net (code "1") (name "/ATX_PG") (class "Default")
      (node (ref "R357") (pin "2") (pinfunction "2_2") (pintype "passive"))
      (node (ref "U87") (pin "6") (pinfunction "S_6") (pintype "passive"))
      (node (ref "U89") (pin "6") (pinfunction "S_6") (pintype "passive"))
    )
    (net (code "2") (name "/AUX_SCL") (class "Default")
      (node (ref "R124") (pin "2") (pinfunction "2_2") (pintype "passive"))
      (node (ref "U38") (pin "6") (pinfunction "SCL_6") (pintype "bidirectional"))
      (node (ref "U87") (pin "4") (pinfunction "A_4") (pintype "passive"))
    )
    (net (code "3") (name "/AUX_SDA") (class "Default")
      (node (ref "R125") (pin "2") (pinfunction "2_2") (pintype "passive"))
      (node (ref "R126") (pin "2") (pinfunction "2_2") (pintype "passive"))
      (node (ref "U38") (pin "5") (pinfunction "SDA_5") (pintype "bidirectional"))
      (node (ref "U89") (pin "4") (pinfunction "A_4") (pintype "passive"))
    )
    (net (code "4") (name "/BOOT_CFG0") (class "Default")
      (node (ref "U2") (pin "A29") (pinfunction "UART0_CTS#_A29") (pintype "input"))
    )
    (net (code "5") (name "/BOOT_CFG1") (class "Default")
      (node (ref "U37") (pin "1") (pinfunction "B1_1") (pintype "passive"))
    )
    (net (code "6") (name "/BOOT_CFG2") (class "Default")
      (node (ref "U39") (pin "1") (pinfunction "B1_1") (pintype "passive"))
    )
    (net (code "7") (name "/BOOT_CFG_DISn") (class "Default")
      (node (ref "R150") (pin "1") (pinfunction "1_1") (pintype "passive"))
      (node (ref "U37") (pin "6") (pinfunction "S_6") (pintype "passive"))
      (node (ref "U39") (pin "6") (pinfunction "S_6") (pintype "passive"))
    )
    (net (code "8") (name "/CPU_RDY") (class "Default")
      (node (ref "U2") (pin "C5") (pinfunction "GPIO29/USB2SUSP_HOLDACK_C5") (pintype "input"))
    )
    (net (code "9") (name "/FTDI_CTRL0") (class "Default")
      (node (ref "R356") (pin "2") (pinfunction "2_2") (pintype "passive"))
    )
    (net (code "10") (name "/FTDI_CTRL1") (class "Default")
      (node (ref "R355") (pin "2") (pinfunction "2_2") (pintype "passive"))
    )
    (net (code "11") (name "/FTDI_CTRL2") (class "Default")
      (node (ref "R354") (pin "2") (pinfunction "2_2") (pintype "passive"))
    )
    (net (code "12") (name "/FTDI_CTRL3") (class "Default")
      (node (ref "R353") (pin "2") (pinfunction "2_2") (pintype "passive"))
    )
    (net (code "14") (name "/FTDI_TCK") (class "Default")
      (node (ref "U33") (pin "16") (pinfunction "ADBUS0_16") (pintype "bidirectional"))
    )
    (net (code "15") (name "/FTDI_TDI") (class "Default")
      (node (ref "U33") (pin "17") (pinfunction "ADBUS1_17") (pintype "bidirectional"))
    )
    (net (code "16") (name "/FTDI_TDO") (class "Default")
      (node (ref "U33") (pin "18") (pinfunction "ADBUS2_18") (pintype "bidirectional"))
    )
    (net (code "17") (name "/FTDI_TMS") (class "Default")
      (node (ref "U33") (pin "19") (pinfunction "ADBUS3_19") (pintype "bidirectional"))
    )
    (net (code "18") (name "/FTDI_TRSTn") (class "Default")
      (node (ref "U33") (pin "21") (pinfunction "ADBUS4_21") (pintype "bidirectional"))
    )
    (net (code "19") (name "/FTDI_USBD_N") (class "Default")
      (node (ref "P3") (pin "2") (pinfunction "2_2") (pintype "bidirectional"))
      (node (ref "SP2") (pin "1") (pinfunction "A_1") (pintype "passive"))
      (node (ref "U33") (pin "7") (pinfunction "DM_7") (pintype "passive"))
    )
    (net (code "20") (name "/FTDI_USBD_P") (class "Default")
      (node (ref "P3") (pin "3") (pinfunction "3_3") (pintype "bidirectional"))
      (node (ref "SP2") (pin "2") (pinfunction "B_2") (pintype "passive"))
      (node (ref "U33") (pin "8") (pinfunction "DP_8") (pintype "passive"))
    )
    (net (code "21") (name "/JTAG_GRAB") (class "Default")
      (node (ref "R243") (pin "2") (pinfunction "2_2") (pintype "passive"))
    )
    (net (code "22") (name "/PB_CTRL") (class "Default")
      (node (ref "R226") (pin "2") (pinfunction "2_2") (pintype "passive"))
    )
    (net (code "23") (name "/PCTRL_EN") (class "Default")
      (node (ref "R139") (pin "2") (pinfunction "2_2") (pintype "passive"))
    )
    (net (code "24") (name "/PCTRL_ON") (class "Default")
      (node (ref "R138") (pin "2") (pinfunction "2_2") (pintype "passive"))
    )
    (net (code "25") (name "/PPC_GPIO0") (class "Default")
      (node (ref "U2") (pin "C6") (pinfunction "GPIO28/USB2TXVAL_C6") (pintype "input"))
    )
    (net (code "26") (name "/PPC_GPIO1") (class "Default")
      (node (ref "U2") (pin "A4") (pinfunction "GPIO27/USB2RXERR_EXTREQ#_A4") (pintype "output"))
    )
    (net (code "27") (name "/PPC_GPIO2") (class "Default")
      (node (ref "U2") (pin "M3") (pinfunction "GPIO30/USB2XCVRSEL_EXTACK#_M3") (pintype "input"))
    )
    (net (code "28") (name "/PPC_GPIO3") (class "Default")
      (node (ref "U2") (pin "P4") (pinfunction "GPIO31/USB2TERMSEL_BUSREQ_P4") (pintype "input"))
    )
    (net (code "30") (name "/PPC_HALT") (class "Default")
      (node (ref "Q25") (pin "1") (pinfunction "G_1") (pintype "passive"))
      (node (ref "R149") (pin "2") (pinfunction "2_2") (pintype "passive"))
      (node (ref "R358") (pin "2") (pinfunction "2_2") (pintype "passive"))
    )
    (net (code "31") (name "/PPC_KILLn") (class "Default")
      (node (ref "Q25") (pin "3") (pinfunction "D_3") (pintype "passive"))
      (node (ref "R62") (pin "1") (pinfunction "1_1") (pintype "passive"))
    )
    (net (code "32") (name "/PPC_SCL") (class "Default")
      (node (ref "P7") (pin "10") (pinfunction "10_10") (pintype "passive"))
      (node (ref "R142") (pin "1") (pinfunction "1_1") (pintype "passive"))
      (node (ref "SP4") (pin "1") (pinfunction "A_1") (pintype "passive"))
      (node (ref "U2") (pin "AB32") (pinfunction "IIC0SCLK_AB32") (pintype "bidirectional"))
      (node (ref "U87") (pin "1") (pinfunction "B1_1") (pintype "passive"))
    )
    (net (code "33") (name "/PPC_SDA") (class "Default")
      (node (ref "P7") (pin "12") (pinfunction "12_12") (pintype "passive"))
      (node (ref "R141") (pin "1") (pinfunction "1_1") (pintype "passive"))
      (node (ref "SP5") (pin "1") (pinfunction "A_1") (pintype "passive"))
      (node (ref "U2") (pin "AB33") (pinfunction "IIC0SDATA_AB33") (pintype "bidirectional"))
      (node (ref "U89") (pin "1") (pinfunction "B1_1") (pintype "passive"))
    )
    (net (code "34") (name "/PPC_USBD_N") (class "Default")
      (node (ref "P4") (pin "2") (pinfunction "2_2") (pintype "bidirectional"))
      (node (ref "SP1") (pin "2") (pinfunction "B_2") (pintype "passive"))
      (node (ref "U2") (pin "J1") (pinfunction "USB2XCVR#_J1") (pintype "bidirectional"))
    )
    (net (code "35") (name "/PPC_USBD_P") (class "Default")
      (node (ref "P4") (pin "3") (pinfunction "3_3") (pintype "bidirectional"))
      (node (ref "SP1") (pin "1") (pinfunction "A_1") (pintype "passive"))
      (node (ref "U2") (pin "J2") (pinfunction "USB2XCVR_J2") (pintype "bidirectional"))
    )
    (net (code "36") (name "/SM_DONE") (class "Default")
      (node (ref "R148") (pin "2") (pinfunction "2_2") (pintype "passive"))
    )
    (net (code "37") (name "/SM_INITn") (class "Default")
      (node (ref "R147") (pin "2") (pinfunction "2_2") (pintype "passive"))
    )
    (net (code "38") (name "/SM_PROGn") (class "Default")
      (node (ref "R144") (pin "2") (pinfunction "2_2") (pintype "passive"))
    )
    (net (code "39") (name "/SM_RDWRn") (class "Default")
      (node (ref "R143") (pin "2") (pinfunction "2_2") (pintype "passive"))
    )
    (net (code "40") (name "/SYS_PORn") (class "Default")
      (node (ref "U31") (pin "6") (pinfunction "S_6") (pintype "passive"))
      (node (ref "U83") (pin "6") (pinfunction "S_6") (pintype "passive"))
    )
    (net (code "41") (name "/SYS_WPn") (class "Default")
      (node (ref "Q11") (pin "1") (pinfunction "G_1") (pintype "passive"))
    )
    (net (code "42") (name "/TRC_HALT") (class "Default")
      (node (ref "R270") (pin "2") (pinfunction "2_2") (pintype "passive"))
    )
    (net (code "43") (name "/UART0_RX") (class "Default")
      (node (ref "R130") (pin "2") (pinfunction "2_2") (pintype "passive"))
      (node (ref "R469") (pin "2") (pinfunction "2_2") (pintype "passive"))
      (node (ref "U83") (pin "1") (pinfunction "B1_1") (pintype "passive"))
    )
    (net (code "44") (name "/UART0_TX") (class "Default")
      (node (ref "R131") (pin "2") (pinfunction "2_2") (pintype "passive"))
      (node (ref "R466") (pin "2") (pinfunction "2_2") (pintype "passive"))
      (node (ref "U31") (pin "1") (pinfunction "B1_1") (pintype "passive"))
    )
    (net (code "45") (name "/UART1_CTSn") (class "Default")
      (node (ref "U36") (pin "10") (pinfunction "R2OUT_10") (pintype "output"))
      (node (ref "U39") (pin "3") (pinfunction "B0_3") (pintype "passive"))
    )
    (net (code "46") (name "/UART1_CTSn-BC2") (class "Default")
      (node (ref "U2") (pin "C28") (pinfunction "UART1_CTS#_C28") (pintype "input"))
      (node (ref "U39") (pin "4") (pinfunction "A_4") (pintype "passive"))
    )
    (net (code "47") (name "/UART1_RTSn") (class "Default")
      (node (ref "U36") (pin "12") (pinfunction "T2IN_12") (pintype "input"))
      (node (ref "U37") (pin "3") (pinfunction "B0_3") (pintype "passive"))
    )
    (net (code "48") (name "/UART1_RTSn-BC1") (class "Default")
      (node (ref "U2") (pin "C29") (pinfunction "UART1_RTS#_C29") (pintype "output"))
      (node (ref "U37") (pin "4") (pinfunction "A_4") (pintype "passive"))
    )
    (net (code "49") (name "/UART1_RX") (class "Default")
      (node (ref "U2") (pin "B28") (pinfunction "UART1_RX_B28") (pintype "input"))
      (node (ref "U36") (pin "15") (pinfunction "R1OUT_15") (pintype "output"))
    )
    (net (code "50") (name "/UART1_TX") (class "Default")
      (node (ref "U2") (pin "D28") (pinfunction "UART1_TX_D28") (pintype "output"))
      (node (ref "U36") (pin "13") (pinfunction "T1IN_13") (pintype "input"))
    )
    (net (code "51") (name "1V8_FTDI") (class "Default")
      (node (ref "C170") (pin "2") (pinfunction "2_2") (pintype "passive"))
      (node (ref "C171") (pin "2") (pinfunction "2_2") (pintype "passive"))
      (node (ref "C185") (pin "2") (pinfunction "2_2") (pintype "passive"))
      (node (ref "U33") (pin "12") (pinfunction "VCORE_12") (pintype "passive"))
      (node (ref "U33") (pin "37") (pinfunction "VCORE_37") (pintype "passive"))
      (node (ref "U33") (pin "49") (pinfunction "VREGOUT_49") (pintype "passive"))
      (node (ref "U33") (pin "64") (pinfunction "VCORE_64") (pintype "passive"))
    )
    (net (code "52") (name "3V3") (class "Default")
      (node (ref "C186") (pin "2") (pinfunction "2_2") (pintype "passive"))
      (node (ref "C196") (pin "2") (pinfunction "2_2") (pintype "passive"))
      (node (ref "C197") (pin "2") (pinfunction "2_2") (pintype "passive"))
      (node (ref "C198") (pin "2") (pinfunction "2_2") (pintype "passive"))
      (node (ref "F7") (pin "2") (pinfunction "2_2") (pintype "passive"))
      (node (ref "R141") (pin "2") (pinfunction "2_2") (pintype "passive"))
      (node (ref "R142") (pin "2") (pinfunction "2_2") (pintype "passive"))
      (node (ref "R145") (pin "2") (pinfunction "2_2") (pintype "passive"))
      (node (ref "R146") (pin "2") (pinfunction "2_2") (pintype "passive"))
      (node (ref "R150") (pin "2") (pinfunction "2_2") (pintype "passive"))
      (node (ref "R62") (pin "2") (pinfunction "2_2") (pintype "passive"))
      (node (ref "U36") (pin "19") (pinfunction "VCC_19") (pintype "passive"))
      (node (ref "U36") (pin "20") (pinfunction "FOFF#_20") (pintype "input"))
      (node (ref "U37") (pin "5") (pinfunction "VCC_5") (pintype "passive"))
      (node (ref "U39") (pin "5") (pinfunction "VCC_5") (pintype "passive"))
      (node (ref "Y8") (pin "1") (pinfunction "E/D_1") (pintype "passive"))
      (node (ref "Y8") (pin "4") (pinfunction "VCC_4") (pintype "power_in"))
    )
    (net (code "53") (name "3V3AUX") (class "Default")
      (node (ref "C172") (pin "2") (pinfunction "2_2") (pintype "passive"))
      (node (ref "C173") (pin "2") (pinfunction "2_2") (pintype "passive"))
      (node (ref "C174") (pin "2") (pinfunction "2_2") (pintype "passive"))
      (node (ref "C175") (pin "2") (pinfunction "2_2") (pintype "passive"))
      (node (ref "C180") (pin "2") (pinfunction "2_2") (pintype "passive"))
      (node (ref "C188") (pin "2") (pinfunction "2_2") (pintype "passive"))
      (node (ref "C191") (pin "2") (pinfunction "2_2") (pintype "passive"))
      (node (ref "C370") (pin "2") (pinfunction "2_2") (pintype "passive"))
      (node (ref "C378") (pin "2") (pinfunction "2_2") (pintype "passive"))
      (node (ref "C380") (pin "2") (pinfunction "2_2") (pintype "passive"))
      (node (ref "C42") (pin "2") (pinfunction "2_2") (pintype "passive"))
      (node (ref "DS28") (pin "2") (pinfunction "A_2") (pintype "passive"))
      (node (ref "L18") (pin "1") (pinfunction "1_1") (pintype "passive"))
      (node (ref "L19") (pin "1") (pinfunction "1_1") (pintype "passive"))
      (node (ref "R132") (pin "2") (pinfunction "2_2") (pintype "passive"))
      (node (ref "R133") (pin "2") (pinfunction "2_2") (pintype "passive"))
      (node (ref "R134") (pin "2") (pinfunction "2_2") (pintype "passive"))
      (node (ref "R140") (pin "2") (pinfunction "2_2") (pintype "passive"))
      (node (ref "R466") (pin "1") (pinfunction "1_1") (pintype "passive"))
      (node (ref "R469") (pin "1") (pinfunction "1_1") (pintype "passive"))
      (node (ref "U31") (pin "5") (pinfunction "VCC_5") (pintype "passive"))
      (node (ref "U33") (pin "20") (pinfunction "VCCIO_20") (pintype "passive"))
      (node (ref "U33") (pin "31") (pinfunction "VCCIO_31") (pintype "passive"))
      (node (ref "U33") (pin "42") (pinfunction "VCCIO_42") (pintype "passive"))
      (node (ref "U33") (pin "50") (pinfunction "VREGIN_50") (pintype "passive"))
      (node (ref "U33") (pin "56") (pinfunction "VCCIO_56") (pintype "passive"))
      (node (ref "U34") (pin "8") (pinfunction "VCC_8") (pintype "power_in"))
      (node (ref "U38") (pin "3") (pinfunction "A2_3") (pintype "input"))
      (node (ref "U38") (pin "8") (pinfunction "VCC_8") (pintype "passive"))
      (node (ref "U83") (pin "5") (pinfunction "VCC_5") (pintype "passive"))
      (node (ref "U87") (pin "5") (pinfunction "VCC_5") (pintype "passive"))
      (node (ref "U89") (pin "5") (pinfunction "VCC_5") (pintype "passive"))
    )
    (net (code "54") (name "5V") (class "Default")
      (node (ref "F6") (pin "2") (pinfunction "2_2") (pintype "passive"))
    )
    (net (code "55") (name "GND") (class "Default")
      (node (ref "C170") (pin "1") (pinfunction "1_1") (pintype "passive"))
      (node (ref "C171") (pin "1") (pinfunction "1_1") (pintype "passive"))
      (node (ref "C172") (pin "1") (pinfunction "1_1") (pintype "passive"))
      (node (ref "C173") (pin "1") (pinfunction "1_1") (pintype "passive"))
      (node (ref "C174") (pin "1") (pinfunction "1_1") (pintype "passive"))
      (node (ref "C175") (pin "1") (pinfunction "1_1") (pintype "passive"))
      (node (ref "C176") (pin "1") (pinfunction "1_1") (pintype "passive"))
      (node (ref "C177") (pin "1") (pinfunction "1_1") (pintype "passive"))
      (node (ref "C178") (pin "1") (pinfunction "1_1") (pintype "passive"))
      (node (ref "C179") (pin "1") (pinfunction "1_1") (pintype "passive"))
      (node (ref "C180") (pin "1") (pinfunction "1_1") (pintype "passive"))
      (node (ref "C182") (pin "2") (pinfunction "2_2") (pintype "passive"))
      (node (ref "C183") (pin "1") (pinfunction "1_1") (pintype "passive"))
      (node (ref "C184") (pin "1") (pinfunction "1_1") (pintype "passive"))
      (node (ref "C185") (pin "1") (pinfunction "1_1") (pintype "passive"))
      (node (ref "C186") (pin "1") (pinfunction "1_1") (pintype "passive"))
      (node (ref "C188") (pin "1") (pinfunction "1_1") (pintype "passive"))
      (node (ref "C189") (pin "1") (pinfunction "1_1") (pintype "passive"))
      (node (ref "C190") (pin "1") (pinfunction "1_1") (pintype "passive"))
      (node (ref "C191") (pin "1") (pinfunction "1_1") (pintype "passive"))
      (node (ref "C192") (pin "1") (pinfunction "1_1") (pintype "passive"))
      (node (ref "C195") (pin "1") (pinfunction "1_1") (pintype "passive"))
      (node (ref "C196") (pin "1") (pinfunction "1_1") (pintype "passive"))
      (node (ref "C197") (pin "1") (pinfunction "1_1") (pintype "passive"))
      (node (ref "C198") (pin "1") (pinfunction "1_1") (pintype "passive"))
      (node (ref "C370") (pin "1") (pinfunction "1_1") (pintype "passive"))
      (node (ref "C378") (pin "1") (pinfunction "1_1") (pintype "passive"))
      (node (ref "C380") (pin "1") (pinfunction "1_1") (pintype "passive"))
      (node (ref "C42") (pin "1") (pinfunction "1_1") (pintype "passive"))
      (node (ref "P3") (pin "4") (pinfunction "4_4") (pintype "power_in"))
      (node (ref "P4") (pin "4") (pinfunction "4_4") (pintype "power_in"))
      (node (ref "P4") (pin "5") (pinfunction "5_5") (pintype "power_in"))
      (node (ref "P4") (pin "6") (pinfunction "6_6") (pintype "power_in"))
      (node (ref "P4") (pin "7") (pinfunction "7_7") (pintype "power_in"))
      (node (ref "P6") (pin "10") (pinfunction "10_10") (pintype "passive"))
      (node (ref "P6") (pin "6") (pinfunction "6_6") (pintype "passive"))
      (node (ref "P6") (pin "7") (pinfunction "7_7") (pintype "passive"))
      (node (ref "P6") (pin "8") (pinfunction "8_8") (pintype "passive"))
      (node (ref "P6") (pin "9") (pinfunction "9_9") (pintype "passive"))
      (node (ref "P7") (pin "1") (pinfunction "1_1") (pintype "passive"))
      (node (ref "P7") (pin "11") (pinfunction "11_11") (pintype "passive"))
      (node (ref "P7") (pin "13") (pinfunction "13_13") (pintype "passive"))
      (node (ref "P7") (pin "14") (pinfunction "14_14") (pintype "passive"))
      (node (ref "P7") (pin "3") (pinfunction "3_3") (pintype "passive"))
      (node (ref "P7") (pin "5") (pinfunction "5_5") (pintype "passive"))
      (node (ref "P7") (pin "7") (pinfunction "7_7") (pintype "passive"))
      (node (ref "P7") (pin "9") (pinfunction "9_9") (pintype "passive"))
      (node (ref "Q11") (pin "2") (pinfunction "S_2") (pintype "passive"))
      (node (ref "Q25") (pin "2") (pinfunction "S_2") (pintype "passive"))
      (node (ref "R128") (pin "2") (pinfunction "2_2") (pintype "passive"))
      (node (ref "R129") (pin "1") (pinfunction "1_1") (pintype "passive"))
      (node (ref "R358") (pin "1") (pinfunction "1_1") (pintype "passive"))
      (node (ref "R492") (pin "1") (pinfunction "1_1") (pintype "passive"))
      (node (ref "R67") (pin "1") (pinfunction "1_1") (pintype "passive"))
      (node (ref "R72") (pin "1") (pinfunction "1_1") (pintype "passive"))
      (node (ref "SP1") (pin "3") (pinfunction "COM_3") (pintype "passive"))
      (node (ref "SP2") (pin "3") (pinfunction "COM_3") (pintype "passive"))
      (node (ref "SP4") (pin "2") (pinfunction "B_2") (pintype "passive"))
      (node (ref "SP5") (pin "2") (pinfunction "B_2") (pintype "passive"))
      (node (ref "SP6") (pin "1") (pinfunction "A_1") (pintype "passive"))
      (node (ref "SP7") (pin "1") (pinfunction "A_1") (pintype "passive"))
      (node (ref "SP8") (pin "1") (pinfunction "A_1") (pintype "passive"))
      (node (ref "U2") (pin "A27") (pinfunction "UARTSERCLK_A27") (pintype "input"))
      (node (ref "U2") (pin "N2") (pinfunction "USB2XTAL_N2") (pintype "output"))
      (node (ref "U31") (pin "2") (pinfunction "GND_2") (pintype "passive"))
      (node (ref "U33") (pin "1") (pinfunction "GND_1") (pintype "passive"))
      (node (ref "U33") (pin "10") (pinfunction "AGND_10") (pintype "input"))
      (node (ref "U33") (pin "11") (pinfunction "GND_11") (pintype "passive"))
      (node (ref "U33") (pin "13") (pinfunction "TEST_13") (pintype "passive"))
      (node (ref "U33") (pin "15") (pinfunction "GND_15") (pintype "passive"))
      (node (ref "U33") (pin "25") (pinfunction "GND_25") (pintype "passive"))
      (node (ref "U33") (pin "35") (pinfunction "GND_35") (pintype "passive"))
      (node (ref "U33") (pin "47") (pinfunction "GND_47") (pintype "passive"))
      (node (ref "U33") (pin "5") (pinfunction "GND_5") (pintype "passive"))
      (node (ref "U33") (pin "51") (pinfunction "GND_51") (pintype "passive"))
      (node (ref "U34") (pin "5") (pinfunction "GND_5") (pintype "power_in"))
      (node (ref "U36") (pin "18") (pinfunction "GND_18") (pintype "passive"))
      (node (ref "U37") (pin "2") (pinfunction "GND_2") (pintype "passive"))
      (node (ref "U38") (pin "1") (pinfunction "A0_1") (pintype "input"))
      (node (ref "U38") (pin "2") (pinfunction "A1_2") (pintype "input"))
      (node (ref "U38") (pin "4") (pinfunction "GND_4") (pintype "passive"))
      (node (ref "U39") (pin "2") (pinfunction "GND_2") (pintype "passive"))
      (node (ref "U83") (pin "2") (pinfunction "GND_2") (pintype "passive"))
      (node (ref "U87") (pin "2") (pinfunction "GND_2") (pintype "passive"))
      (node (ref "U89") (pin "2") (pinfunction "GND_2") (pintype "passive"))
      (node (ref "VR1") (pin "1") (pinfunction "1_1") (pintype "passive"))
      (node (ref "VR2") (pin "1") (pinfunction "1_1") (pintype "passive"))
      (node (ref "Y4") (pin "2") (pinfunction "2_2") (pintype "passive"))
      (node (ref "Y4") (pin "4") (pinfunction "4_4") (pintype "passive"))
      (node (ref "Y8") (pin "2") (pinfunction "GND_2") (pintype "power_in"))
    )
    (net (code "56") (name "Net-(C182-Pad1)") (class "Default")
      (node (ref "C182") (pin "1") (pinfunction "1_1") (pintype "passive"))
      (node (ref "C183") (pin "2") (pinfunction "2_2") (pintype "passive"))
      (node (ref "C184") (pin "2") (pinfunction "2_2") (pintype "passive"))
      (node (ref "F6") (pin "1") (pinfunction "1_1") (pintype "passive"))
      (node (ref "P4") (pin "1") (pinfunction "1_1") (pintype "power_in"))
      (node (ref "VR2") (pin "2") (pinfunction "2_2") (pintype "passive"))
    )
    (net (code "57") (name "Net-(DS28-K)") (class "Default")
      (node (ref "DS28") (pin "1") (pinfunction "K_1") (pintype "passive"))
      (node (ref "R61") (pin "2") (pinfunction "2_2") (pintype "passive"))
    )
    (net (code "58") (name "Net-(F7-Pad1)") (class "Default")
      (node (ref "F7") (pin "1") (pinfunction "1_1") (pintype "passive"))
      (node (ref "P7") (pin "2") (pinfunction "2_2") (pintype "passive"))
    )
    (net (code "59") (name "Net-(P3-Pad5)") (class "Default")
      (node (ref "P3") (pin "5") (pinfunction "5_5") (pintype "power_in"))
      (node (ref "R67") (pin "2") (pinfunction "2_2") (pintype "passive"))
    )
    (net (code "60") (name "Net-(P3-Pad6)") (class "Default")
      (node (ref "P3") (pin "6") (pinfunction "6_6") (pintype "power_in"))
      (node (ref "R72") (pin "2") (pinfunction "2_2") (pintype "passive"))
    )
    (net (code "61") (name "Net-(Q11-D)") (class "Default")
      (node (ref "Q11") (pin "3") (pinfunction "D_3") (pintype "passive"))
      (node (ref "R140") (pin "1") (pinfunction "1_1") (pintype "passive"))
      (node (ref "U38") (pin "7") (pinfunction "WP_7") (pintype "input"))
    )
    (net (code "62") (name "Net-(R127-Pad2)") (class "Default")
      (node (ref "R127") (pin "2") (pinfunction "2_2") (pintype "passive"))
      (node (ref "R491") (pin "2") (pinfunction "2_2") (pintype "passive"))
      (node (ref "R492") (pin "2") (pinfunction "2_2") (pintype "passive"))
    )
    (net (code "63") (name "Net-(SP6-B)") (class "Default")
      (node (ref "P7") (pin "4") (pinfunction "4_4") (pintype "passive"))
      (node (ref "R145") (pin "1") (pinfunction "1_1") (pintype "passive"))
      (node (ref "SP6") (pin "2") (pinfunction "B_2") (pintype "passive"))
      (node (ref "U2") (pin "AC34") (pinfunction "SCPCLKOUT_IIC1SCLK_AC34") (pintype "bidirectional"))
    )
    (net (code "64") (name "Net-(SP7-B)") (class "Default")
      (node (ref "P7") (pin "6") (pinfunction "6_6") (pintype "passive"))
      (node (ref "R146") (pin "1") (pinfunction "1_1") (pintype "passive"))
      (node (ref "SP7") (pin "2") (pinfunction "B_2") (pintype "passive"))
      (node (ref "U2") (pin "AC32") (pinfunction "SCPDI_IIC1SDATA_AC32") (pintype "bidirectional"))
    )
    (net (code "65") (name "Net-(SP8-B)") (class "Default")
      (node (ref "P7") (pin "8") (pinfunction "8_8") (pintype "passive"))
      (node (ref "SP8") (pin "2") (pinfunction "B_2") (pintype "passive"))
      (node (ref "U2") (pin "AB31") (pinfunction "SCPDO_AB31") (pintype "output"))
    )
    (net (code "66") (name "Net-(U2E-NFALE{slash}GPIO15)") (class "Default")
      (node (ref "R143") (pin "1") (pinfunction "1_1") (pintype "passive"))
      (node (ref "U2") (pin "B17") (pinfunction "NFALE/GPIO15_B17") (pintype "bidirectional"))
    )
    (net (code "67") (name "Net-(U2E-NFCLE{slash}GPIO14)") (class "Default")
      (node (ref "R144") (pin "1") (pinfunction "1_1") (pintype "passive"))
      (node (ref "U2") (pin "A18") (pinfunction "NFCLE/GPIO14_A18") (pintype "bidirectional"))
    )
    (net (code "68") (name "Net-(U2E-NFRDYBUSY#{slash}GPIO22)") (class "Default")
      (node (ref "R149") (pin "1") (pinfunction "1_1") (pintype "passive"))
      (node (ref "U2") (pin "A17") (pinfunction "NFRDYBUSY#/GPIO22_A17") (pintype "bidirectional"))
    )
    (net (code "69") (name "Net-(U2E-NFREN#{slash}GPIO12)") (class "Default")
      (node (ref "R147") (pin "1") (pinfunction "1_1") (pintype "passive"))
      (node (ref "U2") (pin "D17") (pinfunction "NFREN#/GPIO12_D17") (pintype "bidirectional"))
    )
    (net (code "70") (name "Net-(U2E-NFWEN#{slash}GPIO13)") (class "Default")
      (node (ref "R148") (pin "1") (pinfunction "1_1") (pintype "passive"))
      (node (ref "U2") (pin "A16") (pinfunction "NFWEN#/GPIO13_A16") (pintype "bidirectional"))
    )
    (net (code "71") (name "Net-(U2E-UART0_RX)") (class "Default")
      (node (ref "U2") (pin "C27") (pinfunction "UART0_RX_C27") (pintype "input"))
      (node (ref "U83") (pin "4") (pinfunction "A_4") (pintype "passive"))
    )
    (net (code "72") (name "Net-(U2E-UART0_TX)") (class "Default")
      (node (ref "U2") (pin "D27") (pinfunction "UART0_TX_D27") (pintype "output"))
      (node (ref "U31") (pin "4") (pinfunction "A_4") (pintype "passive"))
    )
    (net (code "73") (name "Net-(U2F-USB2REXT)") (class "Default")
      (node (ref "R128") (pin "1") (pinfunction "1_1") (pintype "passive"))
      (node (ref "U2") (pin "L3") (pinfunction "USB2REXT_L3") (pintype "output"))
    )
    (net (code "74") (name "Net-(U2F-USB2XTAL#)") (class "Default")
      (node (ref "U2") (pin "N3") (pinfunction "USB2XTAL#_N3") (pintype "output"))
      (node (ref "Y8") (pin "3") (pinfunction "OUT_3") (pintype "output"))
    )
    (net (code "75") (name "Net-(U33-BDBUS0)") (class "Default")
      (node (ref "R124") (pin "1") (pinfunction "1_1") (pintype "passive"))
      (node (ref "U33") (pin "26") (pinfunction "BDBUS0_26") (pintype "bidirectional"))
    )
    (net (code "76") (name "Net-(U33-BDBUS1)") (class "Default")
      (node (ref "R125") (pin "1") (pinfunction "1_1") (pintype "passive"))
      (node (ref "U33") (pin "27") (pinfunction "BDBUS1_27") (pintype "bidirectional"))
    )
    (net (code "77") (name "Net-(U33-BDBUS2)") (class "Default")
      (node (ref "R126") (pin "1") (pinfunction "1_1") (pintype "passive"))
      (node (ref "U33") (pin "28") (pinfunction "BDBUS2_28") (pintype "bidirectional"))
    )
    (net (code "78") (name "Net-(U33-BDBUS3)") (class "Default")
      (node (ref "R270") (pin "1") (pinfunction "1_1") (pintype "passive"))
      (node (ref "U33") (pin "29") (pinfunction "BDBUS3_29") (pintype "bidirectional"))
    )
    (net (code "79") (name "Net-(U33-BDBUS4)") (class "Default")
      (node (ref "R353") (pin "1") (pinfunction "1_1") (pintype "passive"))
      (node (ref "U33") (pin "30") (pinfunction "BDBUS4_30") (pintype "bidirectional"))
    )
    (net (code "80") (name "Net-(U33-BDBUS5)") (class "Default")
      (node (ref "R354") (pin "1") (pinfunction "1_1") (pintype "passive"))
      (node (ref "U33") (pin "32") (pinfunction "BDBUS5_32") (pintype "bidirectional"))
    )
    (net (code "81") (name "Net-(U33-BDBUS6)") (class "Default")
      (node (ref "R355") (pin "1") (pinfunction "1_1") (pintype "passive"))
      (node (ref "U33") (pin "33") (pinfunction "BDBUS6_33") (pintype "bidirectional"))
    )
    (net (code "82") (name "Net-(U33-BDBUS7)") (class "Default")
      (node (ref "R356") (pin "1") (pinfunction "1_1") (pintype "passive"))
      (node (ref "U33") (pin "34") (pinfunction "BDBUS7_34") (pintype "bidirectional"))
    )
    (net (code "83") (name "Net-(U33-CDBUS0)") (class "Default")
      (node (ref "R130") (pin "1") (pinfunction "1_1") (pintype "passive"))
      (node (ref "U33") (pin "38") (pinfunction "CDBUS0_38") (pintype "bidirectional"))
    )
    (net (code "84") (name "Net-(U33-CDBUS1)") (class "Default")
      (node (ref "R131") (pin "1") (pinfunction "1_1") (pintype "passive"))
      (node (ref "U33") (pin "39") (pinfunction "CDBUS1_39") (pintype "bidirectional"))
    )
    (net (code "85") (name "Net-(U33-DDBUS2)") (class "Default")
      (node (ref "R357") (pin "1") (pinfunction "1_1") (pintype "passive"))
      (node (ref "U33") (pin "53") (pinfunction "DDBUS2_53") (pintype "bidirectional"))
    )
    (net (code "86") (name "Net-(U33-DDBUS3)") (class "Default")
      (node (ref "R243") (pin "1") (pinfunction "1_1") (pintype "passive"))
      (node (ref "U33") (pin "54") (pinfunction "DDBUS3_54") (pintype "bidirectional"))
    )
    (net (code "87") (name "Net-(U33-DDBUS4)") (class "Default")
      (node (ref "R138") (pin "1") (pinfunction "1_1") (pintype "passive"))
      (node (ref "U33") (pin "55") (pinfunction "DDBUS4_55") (pintype "bidirectional"))
    )
    (net (code "88") (name "Net-(U33-DDBUS5)") (class "Default")
      (node (ref "R139") (pin "1") (pinfunction "1_1") (pintype "passive"))
      (node (ref "U33") (pin "57") (pinfunction "DDBUS5_57") (pintype "bidirectional"))
    )
    (net (code "89") (name "Net-(U33-DDBUS6)") (class "Default")
      (node (ref "R226") (pin "1") (pinfunction "1_1") (pintype "passive"))
      (node (ref "U33") (pin "58") (pinfunction "DDBUS6_58") (pintype "bidirectional"))
    )
    (net (code "90") (name "Net-(U33-EECLK)") (class "Default")
      (node (ref "R132") (pin "1") (pinfunction "1_1") (pintype "passive"))
      (node (ref "U33") (pin "62") (pinfunction "EECLK_62") (pintype "passive"))
      (node (ref "U34") (pin "2") (pinfunction "CLK_2") (pintype "input"))
    )
    (net (code "91") (name "Net-(U33-EECS)") (class "Default")
      (node (ref "R133") (pin "1") (pinfunction "1_1") (pintype "passive"))
      (node (ref "U33") (pin "63") (pinfunction "EECS_63") (pintype "passive"))
      (node (ref "U34") (pin "1") (pinfunction "CS_1") (pintype "input"))
    )
    (net (code "92") (name "Net-(U33-EEDATA)") (class "Default")
      (node (ref "R137") (pin "2") (pinfunction "2_2") (pintype "passive"))
      (node (ref "U33") (pin "61") (pinfunction "EEDATA_61") (pintype "passive"))
      (node (ref "U34") (pin "3") (pinfunction "DI_3") (pintype "input"))
    )
    (net (code "93") (name "Net-(U33-OSCI)") (class "Default")
      (node (ref "C189") (pin "2") (pinfunction "2_2") (pintype "passive"))
      (node (ref "U33") (pin "2") (pinfunction "OSCI_2") (pintype "passive"))
      (node (ref "Y4") (pin "1") (pinfunction "1_1") (pintype "passive"))
    )
    (net (code "94") (name "Net-(U33-OSCO)") (class "Default")
      (node (ref "C190") (pin "2") (pinfunction "2_2") (pintype "passive"))
      (node (ref "U33") (pin "3") (pinfunction "OSCO_3") (pintype "passive"))
      (node (ref "Y4") (pin "3") (pinfunction "3_3") (pintype "passive"))
    )
    (net (code "95") (name "Net-(U33-REF)") (class "Default")
      (node (ref "R129") (pin "2") (pinfunction "2_2") (pintype "passive"))
      (node (ref "U33") (pin "6") (pinfunction "REF_6") (pintype "passive"))
    )
    (net (code "96") (name "Net-(U33-VPHY)") (class "Default")
      (node (ref "C177") (pin "2") (pinfunction "2_2") (pintype "passive"))
      (node (ref "C179") (pin "2") (pinfunction "2_2") (pintype "passive"))
      (node (ref "L19") (pin "2") (pinfunction "2_2") (pintype "passive"))
      (node (ref "U33") (pin "4") (pinfunction "VPHY_4") (pintype "passive"))
    )
    (net (code "97") (name "Net-(U33-VPLL)") (class "Default")
      (node (ref "C176") (pin "2") (pinfunction "2_2") (pintype "passive"))
      (node (ref "C178") (pin "2") (pinfunction "2_2") (pintype "passive"))
      (node (ref "L18") (pin "2") (pinfunction "2_2") (pintype "passive"))
      (node (ref "U33") (pin "9") (pinfunction "VPLL_9") (pintype "passive"))
    )
    (net (code "98") (name "Net-(U33-~{PWREN})") (class "Default")
      (node (ref "R61") (pin "1") (pinfunction "1_1") (pintype "passive"))
      (node (ref "U33") (pin "60") (pinfunction "~{PWREN}_60") (pintype "passive"))
    )
    (net (code "99") (name "Net-(U33-~{RESET})") (class "Default")
      (node (ref "R491") (pin "1") (pinfunction "1_1") (pintype "passive"))
      (node (ref "U33") (pin "14") (pinfunction "~{RESET}_14") (pintype "passive"))
    )
    (net (code "100") (name "Net-(U34-DO)") (class "Default")
      (node (ref "R134") (pin "1") (pinfunction "1_1") (pintype "passive"))
      (node (ref "R137") (pin "1") (pinfunction "1_1") (pintype "passive"))
      (node (ref "U34") (pin "4") (pinfunction "DO_4") (pintype "output"))
    )
    (net (code "101") (name "Net-(U36-C1N)") (class "Default")
      (node (ref "C193") (pin "2") (pinfunction "2_2") (pintype "passive"))
      (node (ref "U36") (pin "4") (pinfunction "C1N_4") (pintype "passive"))
    )
    (net (code "102") (name "Net-(U36-C1P)") (class "Default")
      (node (ref "C193") (pin "1") (pinfunction "1_1") (pintype "passive"))
      (node (ref "U36") (pin "2") (pinfunction "C1P_2") (pintype "passive"))
    )
    (net (code "103") (name "Net-(U36-C2N)") (class "Default")
      (node (ref "C194") (pin "2") (pinfunction "2_2") (pintype "passive"))
      (node (ref "U36") (pin "6") (pinfunction "C2N_6") (pintype "passive"))
    )
    (net (code "104") (name "Net-(U36-C2P)") (class "Default")
      (node (ref "C194") (pin "1") (pinfunction "1_1") (pintype "passive"))
      (node (ref "U36") (pin "5") (pinfunction "C2P_5") (pintype "passive"))
    )
    (net (code "105") (name "Net-(U36-FON)") (class "Default")
      (node (ref "U36") (pin "11") (pinfunction "INVALID#_11") (pintype "output"))
      (node (ref "U36") (pin "14") (pinfunction "FON_14") (pintype "input"))
    )
    (net (code "106") (name "Net-(U36-R1IN)") (class "Default")
      (node (ref "P6") (pin "3") (pinfunction "3_3") (pintype "passive"))
      (node (ref "U36") (pin "16") (pinfunction "R1IN_16") (pintype "input"))
    )
    (net (code "107") (name "Net-(U36-R2IN)") (class "Default")
      (node (ref "P6") (pin "5") (pinfunction "5_5") (pintype "passive"))
      (node (ref "U36") (pin "9") (pinfunction "R2IN_9") (pintype "input"))
    )
    (net (code "108") (name "Net-(U36-READY)") (class "Default")
      (node (ref "TP39") (pin "1") (pinfunction "1_1") (pintype "passive"))
      (node (ref "U36") (pin "1") (pinfunction "READY_1") (pintype "output"))
    )
    (net (code "109") (name "Net-(U36-T1OUT)") (class "Default")
      (node (ref "P6") (pin "2") (pinfunction "2_2") (pintype "passive"))
      (node (ref "U36") (pin "17") (pinfunction "T1OUT_17") (pintype "output"))
    )
    (net (code "110") (name "Net-(U36-T2OUT)") (class "Default")
      (node (ref "P6") (pin "4") (pinfunction "4_4") (pintype "passive"))
      (node (ref "U36") (pin "8") (pinfunction "T2OUT_8") (pintype "output"))
    )
    (net (code "111") (name "Net-(U36-V+)") (class "Default")
      (node (ref "C192") (pin "2") (pinfunction "2_2") (pintype "passive"))
      (node (ref "U36") (pin "3") (pinfunction "V+_3") (pintype "passive"))
    )
    (net (code "112") (name "Net-(U36-V-)") (class "Default")
      (node (ref "C195") (pin "2") (pinfunction "2_2") (pintype "passive"))
      (node (ref "U36") (pin "7") (pinfunction "V-_7") (pintype "passive"))
    )
    (net (code "113") (name "VBUS_FTDI") (class "Default")
      (node (ref "P3") (pin "1") (pinfunction "1_1") (pintype "power_in"))
      (node (ref "R127") (pin "1") (pinfunction "1_1") (pintype "passive"))
      (node (ref "VR1") (pin "2") (pinfunction "2_2") (pintype "passive"))
    )
    (net (code "114") (name "unconnected-(P6-Pad1)") (class "Default")
      (node (ref "P6") (pin "1") (pinfunction "1_1") (pintype "passive+no_connect"))
    )
    (net (code "115") (name "unconnected-(U2E-UART0_RTS#-PadB29)") (class "Default")
      (node (ref "U2") (pin "B29") (pinfunction "UART0_RTS#_B29") (pintype "output+no_connect"))
    )
    (net (code "116") (name "unconnected-(U2F-GPIO32{slash}USB2OM0-PadR3)") (class "Default")
      (node (ref "U2") (pin "R3") (pinfunction "GPIO32/USB2OM0_R3") (pintype "input+no_connect"))
    )
    (net (code "117") (name "unconnected-(U2F-GPIO33{slash}USB2OM1-PadR4)") (class "Default")
      (node (ref "U2") (pin "R4") (pinfunction "GPIO33/USB2OM1_R4") (pintype "input+no_connect"))
    )
    (net (code "118") (name "unconnected-(U2F-USB2CLK-PadA5)") (class "Default")
      (node (ref "U2") (pin "A5") (pinfunction "USB2CLK_A5") (pintype "output+no_connect"))
    )
    (net (code "119") (name "unconnected-(U2F-USB2LS0_DRVINH1-PadR2)") (class "Default")
      (node (ref "U2") (pin "R2") (pinfunction "USB2LS0_DRVINH1_R2") (pintype "output+no_connect"))
    )
    (net (code "120") (name "unconnected-(U2F-USB2LS1_LEAKTEST_HOLDPRI-PadP1)") (class "Default")
      (node (ref "U2") (pin "P1") (pinfunction "USB2LS1_LEAKTEST_HOLDPRI_P1") (pintype "output+no_connect"))
    )
    (net (code "121") (name "unconnected-(U2F-USB2RXACT_HOLDREQ_RCVINH-PadD7)") (class "Default")
      (node (ref "U2") (pin "D7") (pinfunction "USB2RXACT_HOLDREQ_RCVINH_D7") (pintype "output+no_connect"))
    )
    (net (code "122") (name "unconnected-(U2F-USB2RXVAL_LEAKTEST2-PadC8)") (class "Default")
      (node (ref "U2") (pin "C8") (pinfunction "USB2RXVAL_LEAKTEST2_C8") (pintype "output+no_connect"))
    )
    (net (code "123") (name "unconnected-(U2F-USB2TXRDY_REFEN-PadB6)") (class "Default")
      (node (ref "U2") (pin "B6") (pinfunction "USB2TXRDY_REFEN_B6") (pintype "output+no_connect"))
    )
    (net (code "124") (name "unconnected-(U31-B0-Pad3)") (class "Default")
      (node (ref "U31") (pin "3") (pinfunction "B0_3") (pintype "passive+no_connect"))
    )
    (net (code "125") (name "unconnected-(U33-ADBUS5-Pad22)") (class "Default")
      (node (ref "U33") (pin "22") (pinfunction "ADBUS5_22") (pintype "bidirectional+no_connect"))
    )
    (net (code "126") (name "unconnected-(U33-ADBUS6-Pad23)") (class "Default")
      (node (ref "U33") (pin "23") (pinfunction "ADBUS6_23") (pintype "bidirectional+no_connect"))
    )
    (net (code "127") (name "unconnected-(U33-ADBUS7-Pad24)") (class "Default")
      (node (ref "U33") (pin "24") (pinfunction "ADBUS7_24") (pintype "bidirectional+no_connect"))
    )
    (net (code "128") (name "unconnected-(U33-CDBUS2-Pad40)") (class "Default")
      (node (ref "U33") (pin "40") (pinfunction "CDBUS2_40") (pintype "bidirectional+no_connect"))
    )
    (net (code "129") (name "unconnected-(U33-CDBUS3-Pad41)") (class "Default")
      (node (ref "U33") (pin "41") (pinfunction "CDBUS3_41") (pintype "bidirectional+no_connect"))
    )
    (net (code "130") (name "unconnected-(U33-CDBUS4-Pad43)") (class "Default")
      (node (ref "U33") (pin "43") (pinfunction "CDBUS4_43") (pintype "bidirectional"))
    )
    (net (code "131") (name "unconnected-(U33-CDBUS5-Pad44)") (class "Default")
      (node (ref "U33") (pin "44") (pinfunction "CDBUS5_44") (pintype "bidirectional"))
    )
    (net (code "132") (name "unconnected-(U33-CDBUS6-Pad45)") (class "Default")
      (node (ref "U33") (pin "45") (pinfunction "CDBUS6_45") (pintype "bidirectional+no_connect"))
    )
    (net (code "133") (name "unconnected-(U33-CDBUS7-Pad46)") (class "Default")
      (node (ref "U33") (pin "46") (pinfunction "CDBUS7_46") (pintype "bidirectional+no_connect"))
    )
    (net (code "134") (name "unconnected-(U33-DDBUS0-Pad48)") (class "Default")
      (node (ref "U33") (pin "48") (pinfunction "DDBUS0_48") (pintype "bidirectional+no_connect"))
    )
    (net (code "135") (name "unconnected-(U33-DDBUS1-Pad52)") (class "Default")
      (node (ref "U33") (pin "52") (pinfunction "DDBUS1_52") (pintype "bidirectional+no_connect"))
    )
    (net (code "136") (name "unconnected-(U33-DDBUS7-Pad59)") (class "Default")
      (node (ref "U33") (pin "59") (pinfunction "DDBUS7_59") (pintype "bidirectional+no_connect"))
    )
    (net (code "137") (name "unconnected-(U33-~{SUSPEND}-Pad36)") (class "Default")
      (node (ref "U33") (pin "36") (pinfunction "~{SUSPEND}_36") (pintype "passive+no_connect"))
    )
    (net (code "138") (name "unconnected-(U34-NU-Pad7)") (class "Default")
      (node (ref "U34") (pin "7") (pinfunction "NU_7") (pintype "power_in+no_connect"))
    )
    (net (code "139") (name "unconnected-(U34-ORG-Pad6)") (class "Default")
      (node (ref "U34") (pin "6") (pinfunction "ORG_6") (pintype "power_in+no_connect"))
    )
    (net (code "140") (name "unconnected-(U83-B0-Pad3)") (class "Default")
      (node (ref "U83") (pin "3") (pinfunction "B0_3") (pintype "passive+no_connect"))
    )
    (net (code "141") (name "unconnected-(U87-B0-Pad3)") (class "Default")
      (node (ref "U87") (pin "3") (pinfunction "B0_3") (pintype "passive+no_connect"))
    )
    (net (code "142") (name "unconnected-(U89-B0-Pad3)") (class "Default")
      (node (ref "U89") (pin "3") (pinfunction "B0_3") (pintype "passive+no_connect"))
    )
    (net (code "143") (name "unconnected-(Y4-Pad2)") (class "Default")
      (node (ref "Y4") (pin "2") (pinfunction "2_2") (pintype "passive"))
    )
    (net (code "144") (name "unconnected-(Y4-Pad2)_1") (class "Default")
      (node (ref "Y4") (pin "2") (pinfunction "2_2") (pintype "passive"))
    )
    (net (code "145") (name "unconnected-(Y4-Pad3)") (class "Default")
      (node (ref "Y4") (pin "3") (pinfunction "3_3") (pintype "passive"))
    )
    (net (code "146") (name "unconnected-(Y4-Pad4)") (class "Default")
      (node (ref "Y4") (pin "4") (pinfunction "4_4") (pintype "passive"))
    )
  )
)
